# TCO_v3.net
KiCad netlist of a schematic drawn in EAGLE
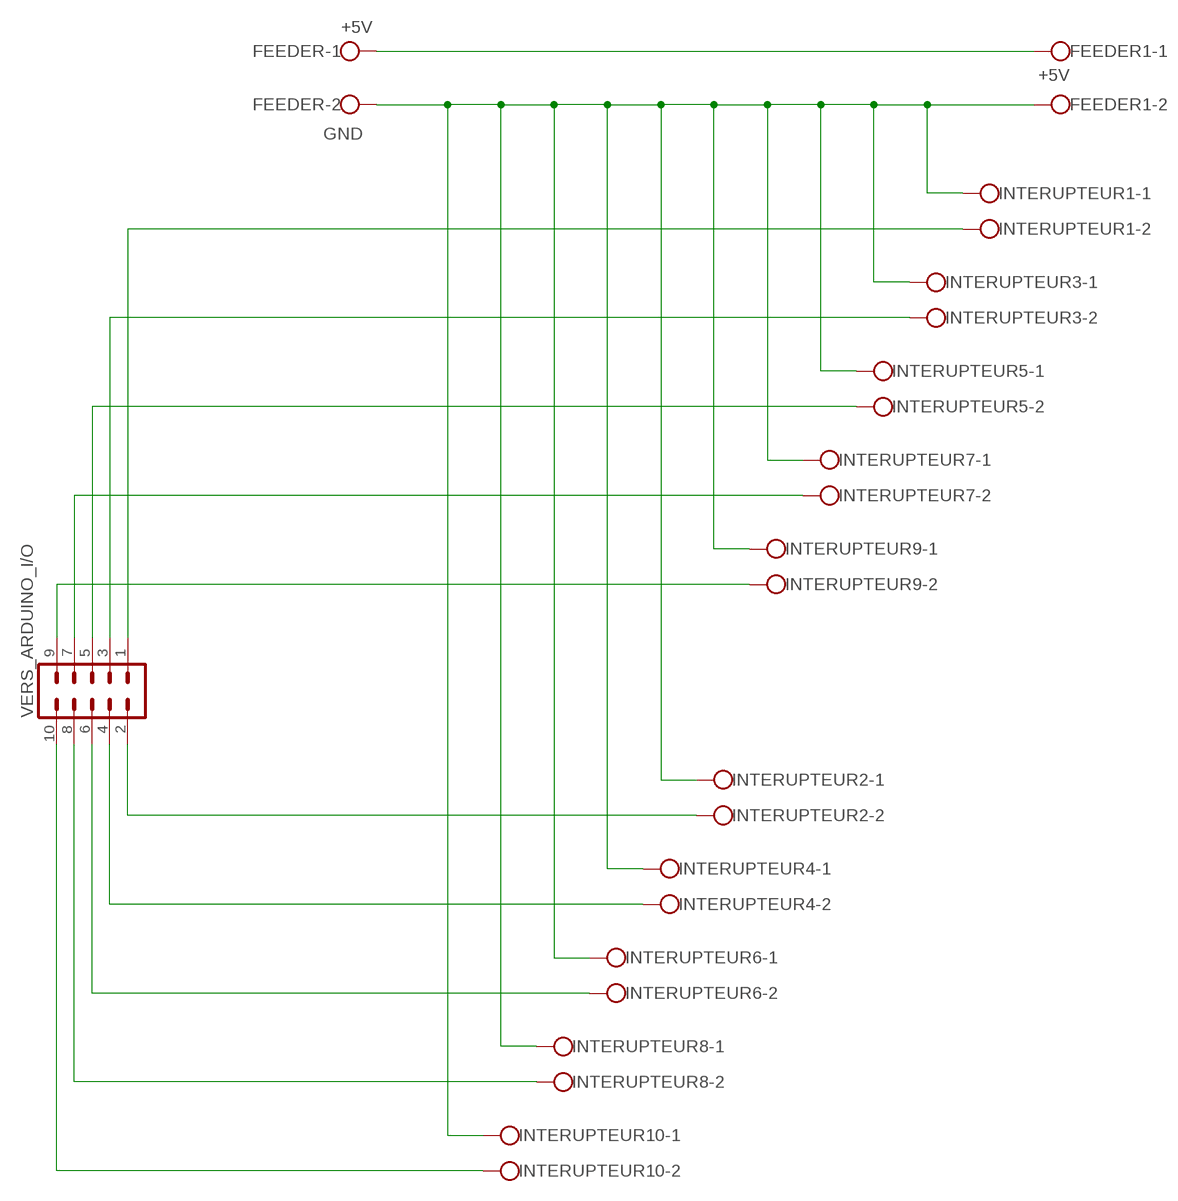
[diagram p0: schematic, sheet 1]

(export (version "E")
  (design (tool "Eeschema 10.0.6"))
  (components
    (comp (ref "FEEDER")
      (value "W237-102")
      (footprint "eagle-import:W237-102")
      (fields (field (name "MPN") "237-102") (field (name "PIN-1") "+5V") (field (name "PIN-2") "GND"))
      (libsource (lib "eagle-import") (part "W237-102"))
    )
    (comp (ref "FEEDER1")
      (value "W237-102")
      (footprint "eagle-import:W237-102")
      (fields (field (name "MPN") "237-102") (field (name "PIN-1") "+5V") (field (name "PIN-2") "GND"))
      (libsource (lib "eagle-import") (part "W237-102"))
    )
    (comp (ref "INTERUPTEUR1")
      (value "W237-102")
      (footprint "eagle-import:W237-102")
      (fields (field (name "MPN") "237-102") (field (name "PIN-1") "+5V") (field (name "PIN-2") "GND"))
      (libsource (lib "eagle-import") (part "W237-102"))
    )
    (comp (ref "INTERUPTEUR2")
      (value "W237-102")
      (footprint "eagle-import:W237-102")
      (fields (field (name "MPN") "237-102") (field (name "PIN-1") "+5V") (field (name "PIN-2") "GND"))
      (libsource (lib "eagle-import") (part "W237-102"))
    )
    (comp (ref "INTERUPTEUR3")
      (value "W237-102")
      (footprint "eagle-import:W237-102")
      (fields (field (name "MPN") "237-102") (field (name "PIN-1") "+5V") (field (name "PIN-2") "GND"))
      (libsource (lib "eagle-import") (part "W237-102"))
    )
    (comp (ref "INTERUPTEUR4")
      (value "W237-102")
      (footprint "eagle-import:W237-102")
      (fields (field (name "MPN") "237-102") (field (name "PIN-1") "+5V") (field (name "PIN-2") "GND"))
      (libsource (lib "eagle-import") (part "W237-102"))
    )
    (comp (ref "INTERUPTEUR5")
      (value "W237-102")
      (footprint "eagle-import:W237-102")
      (fields (field (name "MPN") "237-102") (field (name "PIN-1") "+5V") (field (name "PIN-2") "GND"))
      (libsource (lib "eagle-import") (part "W237-102"))
    )
    (comp (ref "INTERUPTEUR6")
      (value "W237-102")
      (footprint "eagle-import:W237-102")
      (fields (field (name "MPN") "237-102") (field (name "PIN-1") "+5V") (field (name "PIN-2") "GND"))
      (libsource (lib "eagle-import") (part "W237-102"))
    )
    (comp (ref "INTERUPTEUR7")
      (value "W237-102")
      (footprint "eagle-import:W237-102")
      (fields (field (name "MPN") "237-102") (field (name "PIN-1") "+5V") (field (name "PIN-2") "GND"))
      (libsource (lib "eagle-import") (part "W237-102"))
    )
    (comp (ref "INTERUPTEUR8")
      (value "W237-102")
      (footprint "eagle-import:W237-102")
      (fields (field (name "MPN") "237-102") (field (name "PIN-1") "+5V") (field (name "PIN-2") "GND"))
      (libsource (lib "eagle-import") (part "W237-102"))
    )
    (comp (ref "INTERUPTEUR9")
      (value "W237-102")
      (footprint "eagle-import:W237-102")
      (fields (field (name "MPN") "237-102") (field (name "PIN-1") "+5V") (field (name "PIN-2") "GND"))
      (libsource (lib "eagle-import") (part "W237-102"))
    )
    (comp (ref "INTERUPTEUR10")
      (value "W237-102")
      (footprint "eagle-import:W237-102")
      (fields (field (name "MPN") "237-102") (field (name "PIN-1") "+5V") (field (name "PIN-2") "GND"))
      (libsource (lib "eagle-import") (part "W237-102"))
    )
    (comp (ref "VERS_ARDUINO_I/O")
      (value "MA05-2")
      (footprint "eagle-import:MA05-2")
      (libsource (lib "eagle-import") (part "MA05-2"))
    )
  )
  (nets
    (net (code "1") (name "Net-(FEEDER1A-KL)") (class "Default")
      (node (ref "FEEDER") (pin "1") (pinfunction "KL_1") (pintype "passive"))
      (node (ref "FEEDER1") (pin "1") (pinfunction "KL_1") (pintype "passive"))
    )
    (net (code "2") (name "Net-(FEEDER1B-KL)") (class "Default")
      (node (ref "FEEDER") (pin "2") (pinfunction "KL_2") (pintype "passive"))
      (node (ref "FEEDER1") (pin "2") (pinfunction "KL_2") (pintype "passive"))
      (node (ref "INTERUPTEUR1") (pin "1") (pinfunction "KL_1") (pintype "passive"))
      (node (ref "INTERUPTEUR10") (pin "1") (pinfunction "KL_1") (pintype "passive"))
      (node (ref "INTERUPTEUR2") (pin "1") (pinfunction "KL_1") (pintype "passive"))
      (node (ref "INTERUPTEUR3") (pin "1") (pinfunction "KL_1") (pintype "passive"))
      (node (ref "INTERUPTEUR4") (pin "1") (pinfunction "KL_1") (pintype "passive"))
      (node (ref "INTERUPTEUR5") (pin "1") (pinfunction "KL_1") (pintype "passive"))
      (node (ref "INTERUPTEUR6") (pin "1") (pinfunction "KL_1") (pintype "passive"))
      (node (ref "INTERUPTEUR7") (pin "1") (pinfunction "KL_1") (pintype "passive"))
      (node (ref "INTERUPTEUR8") (pin "1") (pinfunction "KL_1") (pintype "passive"))
      (node (ref "INTERUPTEUR9") (pin "1") (pinfunction "KL_1") (pintype "passive"))
    )
    (net (code "3") (name "Net-(INTERUPTEUR1B-KL)") (class "Default")
      (node (ref "INTERUPTEUR1") (pin "2") (pinfunction "KL_2") (pintype "passive"))
      (node (ref "VERS_ARDUINO_I/O") (pin "1") (pinfunction "1_1") (pintype "passive"))
    )
    (net (code "4") (name "Net-(INTERUPTEUR2B-KL)") (class "Default")
      (node (ref "INTERUPTEUR2") (pin "2") (pinfunction "KL_2") (pintype "passive"))
      (node (ref "VERS_ARDUINO_I/O") (pin "2") (pinfunction "2_2") (pintype "passive"))
    )
    (net (code "5") (name "Net-(INTERUPTEUR3B-KL)") (class "Default")
      (node (ref "INTERUPTEUR3") (pin "2") (pinfunction "KL_2") (pintype "passive"))
      (node (ref "VERS_ARDUINO_I/O") (pin "3") (pinfunction "3_3") (pintype "passive"))
    )
    (net (code "6") (name "Net-(INTERUPTEUR4B-KL)") (class "Default")
      (node (ref "INTERUPTEUR4") (pin "2") (pinfunction "KL_2") (pintype "passive"))
      (node (ref "VERS_ARDUINO_I/O") (pin "4") (pinfunction "4_4") (pintype "passive"))
    )
    (net (code "7") (name "Net-(INTERUPTEUR5B-KL)") (class "Default")
      (node (ref "INTERUPTEUR5") (pin "2") (pinfunction "KL_2") (pintype "passive"))
      (node (ref "VERS_ARDUINO_I/O") (pin "5") (pinfunction "5_5") (pintype "passive"))
    )
    (net (code "8") (name "Net-(INTERUPTEUR6B-KL)") (class "Default")
      (node (ref "INTERUPTEUR6") (pin "2") (pinfunction "KL_2") (pintype "passive"))
      (node (ref "VERS_ARDUINO_I/O") (pin "6") (pinfunction "6_6") (pintype "passive"))
    )
    (net (code "9") (name "Net-(INTERUPTEUR7B-KL)") (class "Default")
      (node (ref "INTERUPTEUR7") (pin "2") (pinfunction "KL_2") (pintype "passive"))
      (node (ref "VERS_ARDUINO_I/O") (pin "7") (pinfunction "7_7") (pintype "passive"))
    )
    (net (code "10") (name "Net-(INTERUPTEUR8B-KL)") (class "Default")
      (node (ref "INTERUPTEUR8") (pin "2") (pinfunction "KL_2") (pintype "passive"))
      (node (ref "VERS_ARDUINO_I/O") (pin "8") (pinfunction "8_8") (pintype "passive"))
    )
    (net (code "11") (name "Net-(INTERUPTEUR9B-KL)") (class "Default")
      (node (ref "INTERUPTEUR9") (pin "2") (pinfunction "KL_2") (pintype "passive"))
      (node (ref "VERS_ARDUINO_I/O") (pin "9") (pinfunction "9_9") (pintype "passive"))
    )
    (net (code "12") (name "Net-(INTERUPTEUR10B-KL)") (class "Default")
      (node (ref "INTERUPTEUR10") (pin "2") (pinfunction "KL_2") (pintype "passive"))
      (node (ref "VERS_ARDUINO_I/O") (pin "10") (pinfunction "10_10") (pintype "passive"))
    )
  )
)
